# Sheet1.net
KiCad netlist of a schematic drawn in Altium Designer
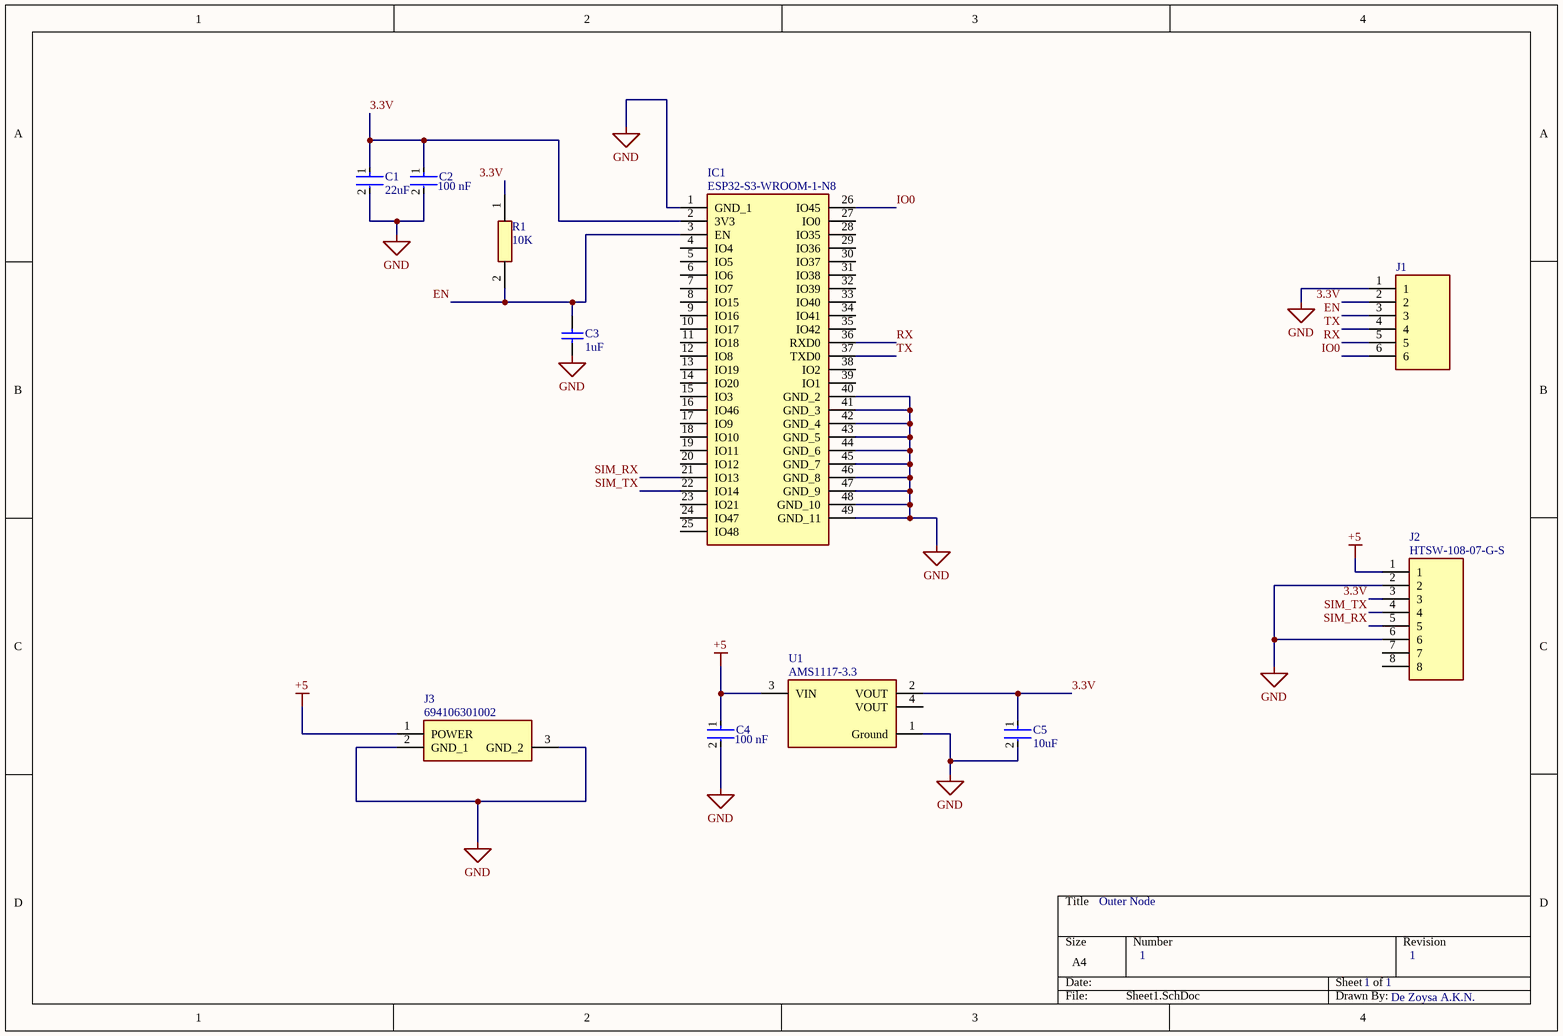
[diagram p0: Sheet1.SchDoc]

(export (version "E")
  (design (tool "Eeschema 10.0.6"))
  (components
    (comp (ref "C1")
      (value "22uF")
      (footprint "FP-CL21-IPC_C")
      (description "CL21 Series 0805 22uF 16V ±20% Tolerance X5R Multilayer Ceramic Chip Capacitor")
      (fields (field (name "TOLERANCE") "20%"))
      (libsource (lib "Altium Content Vault") (part "b4654b650e69147ec39a6b967a45e02"))
    )
    (comp (ref "C2")
      (value "CC0805KRX7R7BB104")
      (footprint "FP-CC0805-0_85-MFG")
      (description "CAP CER 0.1UF 16V X7R 0805")
      (fields
        (field (name "MANUFACTURER") "Yageo")
        (field (name "OCTOPART") "https://octopart.com/cc0805krx7r7bb104-yageo-39467769")
        (field (name "CAPACITANCE") "100 nF")
      )
      (libsource (lib "Altium Content Vault") (part "11868f565c42a9108669ba33697ecf6"))
    )
    (comp (ref "C3")
      (value "1uF")
      (footprint "CAPC2013X140X50LL20T25")
      (fields
        (field (name "PART NUMBER") "0805ZC105KAZ2A")
        (field (name "MANUFACTURER") "AVX Interconnect / Elco")
      )
      (libsource (lib "Altium Content Vault") (part "CAP"))
    )
    (comp (ref "C4")
      (value "CC0805KRX7R7BB104")
      (footprint "FP-CC0805-0_85-MFG")
      (description "CAP CER 0.1UF 16V X7R 0805")
      (fields
        (field (name "MANUFACTURER") "Yageo")
        (field (name "OCTOPART") "https://octopart.com/cc0805krx7r7bb104-yageo-39467769")
        (field (name "CAPACITANCE") "100 nF")
      )
      (libsource (lib "Altium Content Vault") (part "11868f565c42a9108669ba33697ecf6"))
    )
    (comp (ref "C5")
      (value "10uF")
      (footprint "FP-CL21-IPC_B")
      (description "CL21 Series 0805 10uF 16V ±10% Tolerance X5R Multilayer Ceramic Chip Capacitor")
      (fields (field (name "VOLTAGE") "16V") (field (name "TOLERANCE") "10%"))
      (libsource (lib "Altium Content Vault") (part "b4654b650e69147ec39a6b967a45e02"))
    )
    (comp (ref "IC1")
      (value "ESP32-S3-WROOM-1-N8")
      (footprint "SamacSys:ESP32S3WROOM1N8R2")
      (description "Integrated Circuit")
      (fields (field (name "MOUSER PART NUMBER") "356-ESP32-S3WROOM1N8"))
      (libsource (lib "*") (part "ESP32-S3-WROOM-1-N8"))
    )
    (comp (ref "J1")
      (value "22-28-4060")
      (footprint "SamacSys:HDRV6W66P0X254_1X6_1524X249X838P")
      (description "Connector")
      (fields (field (name "MOUSER PART NUMBER") "538-22-28-4060"))
      (libsource (lib "*") (part "22-28-4060"))
    )
    (comp (ref "J2")
      (value "HTSW-108-07-G-S")
      (footprint "SamacSys:HDRV8W64P0X254_1X8_2032X248X838P")
      (description "Connector")
      (fields (field (name "MOUSER PART NUMBER") "200-HTSW10807GS"))
      (libsource (lib "*") (part "HTSW-108-07-G-S"))
    )
    (comp (ref "J3")
      (value "694106301002")
      (footprint "SamacSys:694106301002_1")
      (description "Connector")
      (fields (field (name "MOUSER PART NUMBER") "710-694106301002"))
      (libsource (lib "*") (part "694106301002"))
    )
    (comp (ref "R1")
      (value "10K")
      (footprint "SamacSys:RESC2012X60N")
      (description "Resistor")
      (fields
        (field (name "MANUFACTURER_PART_NUMBER") "CMP0805AFX-1002ELF")
        (field (name "MOUSER PART NUMBER") "652-CMP0805AFX-1002L")
      )
      (libsource (lib "*") (part "CMP0805AFX-1002ELF"))
    )
    (comp (ref "U1")
      (value "AMS1117-3.3")
      (footprint "FP-AMS1117-IPC_C")
      (description "LDO Voltage Regulators 1A, 3.3V")
      (fields
        (field (name "OCTOPART") "https://octopart.com/ams1117-3.3-advanced+monolithic+systems-25899300")
        (field (name "MANUFACTURER") "Advanced Monolithic Systems")
      )
      (libsource (lib "Altium Content Vault") (part "8bdbb5f8e77002000e30dd2845d0354"))
    )
  )
  (nets
    (net (code "1") (name "+5") (class "Default")
      (node (ref "C4") (pin "1") (pinfunction "1_1") (pintype "passive"))
      (node (ref "J2") (pin "1") (pinfunction "1_1") (pintype "passive"))
      (node (ref "J3") (pin "1") (pinfunction "POWER_1") (pintype "passive"))
      (node (ref "U1") (pin "3") (pinfunction "VIN_3") (pintype "power_in"))
    )
    (net (code "2") (name "/3.3V") (class "Default")
      (node (ref "C1") (pin "1") (pinfunction "1_1") (pintype "passive"))
      (node (ref "C2") (pin "1") (pinfunction "1_1") (pintype "passive"))
      (node (ref "C5") (pin "1") (pinfunction "1_1") (pintype "passive"))
      (node (ref "IC1") (pin "2") (pinfunction "3V3_2") (pintype "passive"))
      (node (ref "J1") (pin "2") (pinfunction "2_2") (pintype "passive"))
      (node (ref "J2") (pin "3") (pinfunction "3_3") (pintype "passive"))
      (node (ref "R1") (pin "1") (pinfunction "1_1") (pintype "passive"))
      (node (ref "U1") (pin "2") (pinfunction "VOUT_2") (pintype "passive"))
    )
    (net (code "3") (name "/EN") (class "Default")
      (node (ref "C3") (pin "2") (pinfunction "2_2") (pintype "passive"))
      (node (ref "IC1") (pin "3") (pinfunction "EN_3") (pintype "passive"))
      (node (ref "J1") (pin "3") (pinfunction "3_3") (pintype "passive"))
      (node (ref "R1") (pin "2") (pinfunction "2_2") (pintype "passive"))
    )
    (net (code "4") (name "/IO0") (class "Default")
      (node (ref "IC1") (pin "26") (pinfunction "IO45_26") (pintype "passive"))
      (node (ref "J1") (pin "6") (pinfunction "6_6") (pintype "passive"))
    )
    (net (code "5") (name "/RX") (class "Default")
      (node (ref "IC1") (pin "36") (pinfunction "RXD0_36") (pintype "passive"))
      (node (ref "J1") (pin "5") (pinfunction "5_5") (pintype "passive"))
    )
    (net (code "6") (name "/SIM_RX") (class "Default")
      (node (ref "IC1") (pin "21") (pinfunction "IO13_21") (pintype "passive"))
      (node (ref "J2") (pin "5") (pinfunction "5_5") (pintype "passive"))
    )
    (net (code "7") (name "/SIM_TX") (class "Default")
      (node (ref "IC1") (pin "22") (pinfunction "IO14_22") (pintype "passive"))
      (node (ref "J2") (pin "4") (pinfunction "4_4") (pintype "passive"))
    )
    (net (code "8") (name "/TX") (class "Default")
      (node (ref "IC1") (pin "37") (pinfunction "TXD0_37") (pintype "passive"))
      (node (ref "J1") (pin "4") (pinfunction "4_4") (pintype "passive"))
    )
    (net (code "9") (name "GND") (class "Default")
      (node (ref "C1") (pin "2") (pinfunction "2_2") (pintype "passive"))
      (node (ref "C2") (pin "2") (pinfunction "2_2") (pintype "passive"))
      (node (ref "C3") (pin "1") (pinfunction "1_1") (pintype "passive"))
      (node (ref "C4") (pin "2") (pinfunction "2_2") (pintype "passive"))
      (node (ref "C5") (pin "2") (pinfunction "2_2") (pintype "passive"))
      (node (ref "IC1") (pin "1") (pinfunction "GND_1_1") (pintype "passive"))
      (node (ref "IC1") (pin "40") (pinfunction "GND_2_40") (pintype "passive"))
      (node (ref "IC1") (pin "41") (pinfunction "GND_3_41") (pintype "passive"))
      (node (ref "IC1") (pin "42") (pinfunction "GND_4_42") (pintype "passive"))
      (node (ref "IC1") (pin "43") (pinfunction "GND_5_43") (pintype "passive"))
      (node (ref "IC1") (pin "44") (pinfunction "GND_6_44") (pintype "passive"))
      (node (ref "IC1") (pin "45") (pinfunction "GND_7_45") (pintype "passive"))
      (node (ref "IC1") (pin "46") (pinfunction "GND_8_46") (pintype "passive"))
      (node (ref "IC1") (pin "47") (pinfunction "GND_9_47") (pintype "passive"))
      (node (ref "IC1") (pin "48") (pinfunction "GND_10_48") (pintype "passive"))
      (node (ref "IC1") (pin "49") (pinfunction "GND_11_49") (pintype "passive"))
      (node (ref "J1") (pin "1") (pinfunction "1_1") (pintype "passive"))
      (node (ref "J2") (pin "2") (pinfunction "2_2") (pintype "passive"))
      (node (ref "J2") (pin "6") (pinfunction "6_6") (pintype "passive"))
      (node (ref "J3") (pin "2") (pinfunction "GND_1_2") (pintype "passive"))
      (node (ref "J3") (pin "3") (pinfunction "GND_2_3") (pintype "passive"))
      (node (ref "U1") (pin "1") (pinfunction "Ground_1") (pintype "power_in"))
    )
    (net (code "10") (name "unconnected-(IC1-IO0-Pad27)") (class "Default")
      (node (ref "IC1") (pin "27") (pinfunction "IO0_27") (pintype "passive"))
    )
    (net (code "11") (name "unconnected-(IC1-IO1-Pad39)") (class "Default")
      (node (ref "IC1") (pin "39") (pinfunction "IO1_39") (pintype "passive"))
    )
    (net (code "12") (name "unconnected-(IC1-IO2-Pad38)") (class "Default")
      (node (ref "IC1") (pin "38") (pinfunction "IO2_38") (pintype "passive"))
    )
    (net (code "13") (name "unconnected-(IC1-IO3-Pad15)") (class "Default")
      (node (ref "IC1") (pin "15") (pinfunction "IO3_15") (pintype "passive"))
    )
    (net (code "14") (name "unconnected-(IC1-IO4-Pad4)") (class "Default")
      (node (ref "IC1") (pin "4") (pinfunction "IO4_4") (pintype "passive"))
    )
    (net (code "15") (name "unconnected-(IC1-IO5-Pad5)") (class "Default")
      (node (ref "IC1") (pin "5") (pinfunction "IO5_5") (pintype "passive"))
    )
    (net (code "16") (name "unconnected-(IC1-IO6-Pad6)") (class "Default")
      (node (ref "IC1") (pin "6") (pinfunction "IO6_6") (pintype "passive"))
    )
    (net (code "17") (name "unconnected-(IC1-IO7-Pad7)") (class "Default")
      (node (ref "IC1") (pin "7") (pinfunction "IO7_7") (pintype "passive"))
    )
    (net (code "18") (name "unconnected-(IC1-IO8-Pad12)") (class "Default")
      (node (ref "IC1") (pin "12") (pinfunction "IO8_12") (pintype "passive"))
    )
    (net (code "19") (name "unconnected-(IC1-IO9-Pad17)") (class "Default")
      (node (ref "IC1") (pin "17") (pinfunction "IO9_17") (pintype "passive"))
    )
    (net (code "20") (name "unconnected-(IC1-IO10-Pad18)") (class "Default")
      (node (ref "IC1") (pin "18") (pinfunction "IO10_18") (pintype "passive"))
    )
    (net (code "21") (name "unconnected-(IC1-IO11-Pad19)") (class "Default")
      (node (ref "IC1") (pin "19") (pinfunction "IO11_19") (pintype "passive"))
    )
    (net (code "22") (name "unconnected-(IC1-IO12-Pad20)") (class "Default")
      (node (ref "IC1") (pin "20") (pinfunction "IO12_20") (pintype "passive"))
    )
    (net (code "23") (name "unconnected-(IC1-IO15-Pad8)") (class "Default")
      (node (ref "IC1") (pin "8") (pinfunction "IO15_8") (pintype "passive"))
    )
    (net (code "24") (name "unconnected-(IC1-IO16-Pad9)") (class "Default")
      (node (ref "IC1") (pin "9") (pinfunction "IO16_9") (pintype "passive"))
    )
    (net (code "25") (name "unconnected-(IC1-IO17-Pad10)") (class "Default")
      (node (ref "IC1") (pin "10") (pinfunction "IO17_10") (pintype "passive"))
    )
    (net (code "26") (name "unconnected-(IC1-IO18-Pad11)") (class "Default")
      (node (ref "IC1") (pin "11") (pinfunction "IO18_11") (pintype "passive"))
    )
    (net (code "27") (name "unconnected-(IC1-IO19-Pad13)") (class "Default")
      (node (ref "IC1") (pin "13") (pinfunction "IO19_13") (pintype "passive"))
    )
    (net (code "28") (name "unconnected-(IC1-IO20-Pad14)") (class "Default")
      (node (ref "IC1") (pin "14") (pinfunction "IO20_14") (pintype "passive"))
    )
    (net (code "29") (name "unconnected-(IC1-IO21-Pad23)") (class "Default")
      (node (ref "IC1") (pin "23") (pinfunction "IO21_23") (pintype "passive"))
    )
    (net (code "30") (name "unconnected-(IC1-IO35-Pad28)") (class "Default")
      (node (ref "IC1") (pin "28") (pinfunction "IO35_28") (pintype "passive"))
    )
    (net (code "31") (name "unconnected-(IC1-IO36-Pad29)") (class "Default")
      (node (ref "IC1") (pin "29") (pinfunction "IO36_29") (pintype "passive"))
    )
    (net (code "32") (name "unconnected-(IC1-IO37-Pad30)") (class "Default")
      (node (ref "IC1") (pin "30") (pinfunction "IO37_30") (pintype "passive"))
    )
    (net (code "33") (name "unconnected-(IC1-IO38-Pad31)") (class "Default")
      (node (ref "IC1") (pin "31") (pinfunction "IO38_31") (pintype "passive"))
    )
    (net (code "34") (name "unconnected-(IC1-IO39-Pad32)") (class "Default")
      (node (ref "IC1") (pin "32") (pinfunction "IO39_32") (pintype "passive"))
    )
    (net (code "35") (name "unconnected-(IC1-IO40-Pad33)") (class "Default")
      (node (ref "IC1") (pin "33") (pinfunction "IO40_33") (pintype "passive"))
    )
    (net (code "36") (name "unconnected-(IC1-IO41-Pad34)") (class "Default")
      (node (ref "IC1") (pin "34") (pinfunction "IO41_34") (pintype "passive"))
    )
    (net (code "37") (name "unconnected-(IC1-IO42-Pad35)") (class "Default")
      (node (ref "IC1") (pin "35") (pinfunction "IO42_35") (pintype "passive"))
    )
    (net (code "38") (name "unconnected-(IC1-IO46-Pad16)") (class "Default")
      (node (ref "IC1") (pin "16") (pinfunction "IO46_16") (pintype "passive"))
    )
    (net (code "39") (name "unconnected-(IC1-IO47-Pad24)") (class "Default")
      (node (ref "IC1") (pin "24") (pinfunction "IO47_24") (pintype "passive"))
    )
    (net (code "40") (name "unconnected-(IC1-IO48-Pad25)") (class "Default")
      (node (ref "IC1") (pin "25") (pinfunction "IO48_25") (pintype "passive"))
    )
    (net (code "41") (name "unconnected-(J2-Pad7)") (class "Default")
      (node (ref "J2") (pin "7") (pinfunction "7_7") (pintype "passive"))
    )
    (net (code "42") (name "unconnected-(J2-Pad8)") (class "Default")
      (node (ref "J2") (pin "8") (pinfunction "8_8") (pintype "passive"))
    )
    (net (code "43") (name "unconnected-(U1-VOUT-Pad4)") (class "Default")
      (node (ref "U1") (pin "4") (pinfunction "VOUT_4") (pintype "passive"))
    )
  )
)
